# PF6_FilterMode.net
KiCad netlist of a schematic drawn in Altium Designer
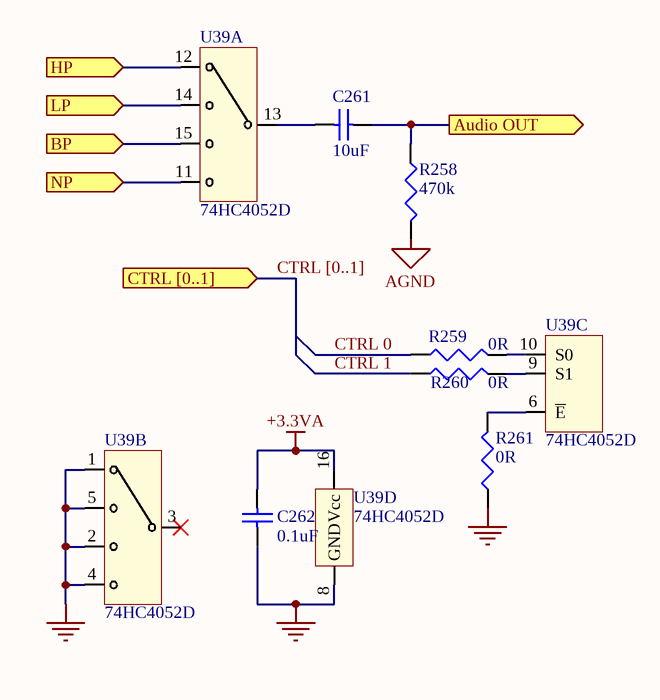
[diagram p0: PF6_FilterMode.SchDoc]

(export (version "E")
  (design (tool "Eeschema 10.0.6"))
  (components
    (comp (ref "C261")
      (value "10uF")
      (footprint "CAPC1608X08")
      (description "Capacitor (Semiconductor SIM Model)")
      (libsource (lib "Michel") (part "Cap Semi"))
    )
    (comp (ref "C262")
      (value "0.1uF")
      (footprint "CAPC1608X08")
      (description "Capacitor (Semiconductor SIM Model)")
      (libsource (lib "Michel") (part "Cap Semi"))
    )
    (comp (ref "R258")
      (value "470k")
      (footprint "RESC1608X05")
      (description "Resistor")
      (libsource (lib "Michel") (part "Res3"))
    )
    (comp (ref "R259")
      (value "0R")
      (footprint "RESC1608X05")
      (description "Resistor")
      (libsource (lib "Michel") (part "Res3"))
    )
    (comp (ref "R260")
      (value "0R")
      (footprint "RESC1608X05")
      (description "Resistor")
      (libsource (lib "Michel") (part "Res3"))
    )
    (comp (ref "R261")
      (value "0R")
      (footprint "RESC1608X05")
      (description "Resistor")
      (libsource (lib "Michel") (part "Res3"))
    )
    (comp (ref "U39")
      (value "74HC4052D")
      (footprint "SOT109-1-M")
      (description "Dual 4:1 Multiplexer")
      (libsource (lib "Michel") (part "74HC4052D"))
    )
  )
  (nets
    (net (code "1") (name "+3.3VA") (class "Default")
      (node (ref "C262") (pin "1") (pinfunction "1_1") (pintype "passive"))
      (node (ref "U39") (pin "16") (pinfunction "Vcc_16") (pintype "power_in"))
    )
    (net (code "2") (name "/Audio OUT") (class "Default")
      (node (ref "C261") (pin "1") (pinfunction "1_1") (pintype "passive"))
      (node (ref "R258") (pin "1") (pinfunction "1_1") (pintype "passive"))
    )
    (net (code "3") (name "/BP") (class "Default")
      (node (ref "U39") (pin "15") (pinfunction "1Y2_15") (pintype "passive"))
    )
    (net (code "4") (name "/CTRL 0") (class "Default")
      (node (ref "R259") (pin "1") (pinfunction "1_1") (pintype "passive"))
    )
    (net (code "5") (name "/CTRL 1") (class "Default")
      (node (ref "R260") (pin "1") (pinfunction "1_1") (pintype "passive"))
    )
    (net (code "6") (name "/HP") (class "Default")
      (node (ref "U39") (pin "12") (pinfunction "1Y0_12") (pintype "passive"))
    )
    (net (code "7") (name "/LP") (class "Default")
      (node (ref "U39") (pin "14") (pinfunction "1Y1_14") (pintype "passive"))
    )
    (net (code "8") (name "/NP") (class "Default")
      (node (ref "U39") (pin "11") (pinfunction "1Y3_11") (pintype "passive"))
    )
    (net (code "10") (name "AGND") (class "Default")
      (node (ref "R258") (pin "2") (pinfunction "2_2") (pintype "passive"))
    )
    (net (code "11") (name "GND") (class "Default")
      (node (ref "C262") (pin "2") (pinfunction "2_2") (pintype "passive"))
      (node (ref "R261") (pin "1") (pinfunction "1_1") (pintype "passive"))
      (node (ref "U39") (pin "1") (pinfunction "2Y0_1") (pintype "passive"))
      (node (ref "U39") (pin "2") (pinfunction "2Y2_2") (pintype "passive"))
      (node (ref "U39") (pin "4") (pinfunction "2Y3_4") (pintype "passive"))
      (node (ref "U39") (pin "5") (pinfunction "2Y1_5") (pintype "passive"))
      (node (ref "U39") (pin "8") (pinfunction "GND_8") (pintype "power_in"))
    )
    (net (code "12") (name "Net-(U39A-1Z)") (class "Default")
      (node (ref "C261") (pin "2") (pinfunction "2_2") (pintype "passive"))
      (node (ref "U39") (pin "13") (pinfunction "1Z_13") (pintype "passive"))
    )
    (net (code "13") (name "Net-(U39C-S0)") (class "Default")
      (node (ref "R259") (pin "2") (pinfunction "2_2") (pintype "passive"))
      (node (ref "U39") (pin "10") (pinfunction "S0_10") (pintype "passive"))
    )
    (net (code "14") (name "Net-(U39C-S1)") (class "Default")
      (node (ref "R260") (pin "2") (pinfunction "2_2") (pintype "passive"))
      (node (ref "U39") (pin "9") (pinfunction "S1_9") (pintype "passive"))
    )
    (net (code "15") (name "Net-(U39C-~{E})") (class "Default")
      (node (ref "R261") (pin "2") (pinfunction "2_2") (pintype "passive"))
      (node (ref "U39") (pin "6") (pinfunction "~{E}_6") (pintype "passive"))
    )
    (net (code "16") (name "unconnected-(U39B-2Z-Pad3)") (class "Default")
      (node (ref "U39") (pin "3") (pinfunction "2Z_3") (pintype "passive+no_connect"))
    )
  )
)
